# sk9822.net
KiCad netlist of a schematic drawn in Altium Designer
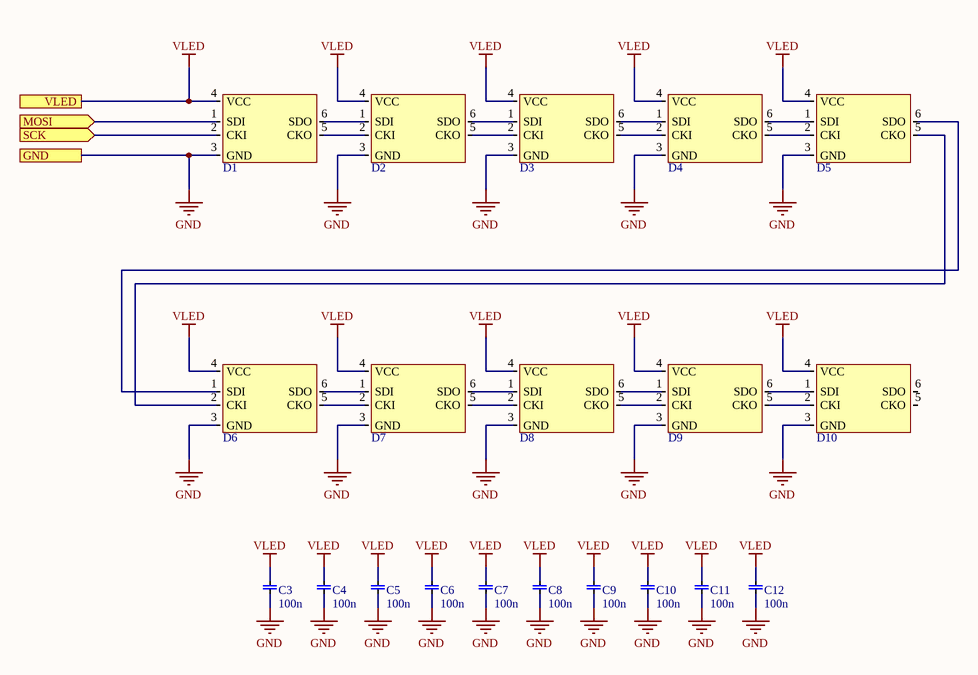
[diagram p0: sk9822.SchDoc]

(export (version "E")
  (design (tool "Eeschema 10.0.6"))
  (components
    (comp (ref "C3")
      (value "100n")
      (footprint "1206, capasitor")
      (fields
        (field (name "JLCPCB PART #") "C24497")
        (field (name "MANUFACTURER PART NUMBER") "CL31B104KBCNNNC")
        (field (name "Comment") "1206, capacitor")
      )
      (libsource (lib "jclib") (part "1206, capacitor"))
    )
    (comp (ref "C4")
      (value "100n")
      (footprint "1206, capasitor")
      (fields
        (field (name "JLCPCB PART #") "C24497")
        (field (name "MANUFACTURER PART NUMBER") "CL31B104KBCNNNC")
        (field (name "Comment") "1206, capacitor")
      )
      (libsource (lib "jclib") (part "1206, capacitor"))
    )
    (comp (ref "C5")
      (value "100n")
      (footprint "1206, capasitor")
      (fields
        (field (name "JLCPCB PART #") "C24497")
        (field (name "MANUFACTURER PART NUMBER") "CL31B104KBCNNNC")
        (field (name "Comment") "1206, capacitor")
      )
      (libsource (lib "jclib") (part "1206, capacitor"))
    )
    (comp (ref "C6")
      (value "100n")
      (footprint "1206, capasitor")
      (fields
        (field (name "JLCPCB PART #") "C24497")
        (field (name "MANUFACTURER PART NUMBER") "CL31B104KBCNNNC")
        (field (name "Comment") "1206, capacitor")
      )
      (libsource (lib "jclib") (part "1206, capacitor"))
    )
    (comp (ref "C7")
      (value "100n")
      (footprint "1206, capasitor")
      (fields
        (field (name "JLCPCB PART #") "C24497")
        (field (name "MANUFACTURER PART NUMBER") "CL31B104KBCNNNC")
        (field (name "Comment") "1206, capacitor")
      )
      (libsource (lib "jclib") (part "1206, capacitor"))
    )
    (comp (ref "C8")
      (value "100n")
      (footprint "1206, capasitor")
      (fields
        (field (name "JLCPCB PART #") "C24497")
        (field (name "MANUFACTURER PART NUMBER") "CL31B104KBCNNNC")
        (field (name "Comment") "1206, capacitor")
      )
      (libsource (lib "jclib") (part "1206, capacitor"))
    )
    (comp (ref "C9")
      (value "100n")
      (footprint "1206, capasitor")
      (fields
        (field (name "JLCPCB PART #") "C24497")
        (field (name "MANUFACTURER PART NUMBER") "CL31B104KBCNNNC")
        (field (name "Comment") "1206, capacitor")
      )
      (libsource (lib "jclib") (part "1206, capacitor"))
    )
    (comp (ref "C10")
      (value "100n")
      (footprint "1206, capasitor")
      (fields
        (field (name "JLCPCB PART #") "C24497")
        (field (name "MANUFACTURER PART NUMBER") "CL31B104KBCNNNC")
        (field (name "Comment") "1206, capacitor")
      )
      (libsource (lib "jclib") (part "1206, capacitor"))
    )
    (comp (ref "C11")
      (value "100n")
      (footprint "1206, capasitor")
      (fields
        (field (name "JLCPCB PART #") "C24497")
        (field (name "MANUFACTURER PART NUMBER") "CL31B104KBCNNNC")
        (field (name "Comment") "1206, capacitor")
      )
      (libsource (lib "jclib") (part "1206, capacitor"))
    )
    (comp (ref "C12")
      (value "100n")
      (footprint "1206, capasitor")
      (fields
        (field (name "JLCPCB PART #") "C24497")
        (field (name "MANUFACTURER PART NUMBER") "CL31B104KBCNNNC")
        (field (name "Comment") "1206, capacitor")
      )
      (libsource (lib "jclib") (part "1206, capacitor"))
    )
    (comp (ref "D1")
      (value "Neo - SK9822")
      (footprint "SK9822")
      (fields (field (name "JLCPCB PART #") "C2829089") (field (name "MANUFACTURER PART NUMBER") "SK9822"))
      (libsource (lib "jclib") (part "Neo - SK9822"))
    )
    (comp (ref "D2")
      (value "Neo - SK9822")
      (footprint "SK9822")
      (fields (field (name "JLCPCB PART #") "C2829089") (field (name "MANUFACTURER PART NUMBER") "SK9822"))
      (libsource (lib "jclib") (part "Neo - SK9822"))
    )
    (comp (ref "D3")
      (value "Neo - SK9822")
      (footprint "SK9822")
      (fields (field (name "JLCPCB PART #") "C2829089") (field (name "MANUFACTURER PART NUMBER") "SK9822"))
      (libsource (lib "jclib") (part "Neo - SK9822"))
    )
    (comp (ref "D4")
      (value "Neo - SK9822")
      (footprint "SK9822")
      (fields (field (name "JLCPCB PART #") "C2829089") (field (name "MANUFACTURER PART NUMBER") "SK9822"))
      (libsource (lib "jclib") (part "Neo - SK9822"))
    )
    (comp (ref "D5")
      (value "Neo - SK9822")
      (footprint "SK9822")
      (fields (field (name "JLCPCB PART #") "C2829089") (field (name "MANUFACTURER PART NUMBER") "SK9822"))
      (libsource (lib "jclib") (part "Neo - SK9822"))
    )
    (comp (ref "D6")
      (value "Neo - SK9822")
      (footprint "SK9822")
      (fields (field (name "JLCPCB PART #") "C2829089") (field (name "MANUFACTURER PART NUMBER") "SK9822"))
      (libsource (lib "jclib") (part "Neo - SK9822"))
    )
    (comp (ref "D7")
      (value "Neo - SK9822")
      (footprint "SK9822")
      (fields (field (name "JLCPCB PART #") "C2829089") (field (name "MANUFACTURER PART NUMBER") "SK9822"))
      (libsource (lib "jclib") (part "Neo - SK9822"))
    )
    (comp (ref "D8")
      (value "Neo - SK9822")
      (footprint "SK9822")
      (fields (field (name "JLCPCB PART #") "C2829089") (field (name "MANUFACTURER PART NUMBER") "SK9822"))
      (libsource (lib "jclib") (part "Neo - SK9822"))
    )
    (comp (ref "D9")
      (value "Neo - SK9822")
      (footprint "SK9822")
      (fields (field (name "JLCPCB PART #") "C2829089") (field (name "MANUFACTURER PART NUMBER") "SK9822"))
      (libsource (lib "jclib") (part "Neo - SK9822"))
    )
    (comp (ref "D10")
      (value "Neo - SK9822")
      (footprint "SK9822")
      (fields (field (name "JLCPCB PART #") "C2829089") (field (name "MANUFACTURER PART NUMBER") "SK9822"))
      (libsource (lib "jclib") (part "Neo - SK9822"))
    )
  )
  (nets
    (net (code "1") (name "/MOSI") (class "Default")
      (node (ref "D1") (pin "1") (pinfunction "SDI_1") (pintype "passive"))
    )
    (net (code "2") (name "/SCK") (class "Default")
      (node (ref "D1") (pin "2") (pinfunction "CKI_2") (pintype "passive"))
    )
    (net (code "3") (name "GND") (class "Default")
      (node (ref "C10") (pin "0") (pinfunction "0_0") (pintype "passive"))
      (node (ref "C11") (pin "0") (pinfunction "0_0") (pintype "passive"))
      (node (ref "C12") (pin "0") (pinfunction "0_0") (pintype "passive"))
      (node (ref "C3") (pin "0") (pinfunction "0_0") (pintype "passive"))
      (node (ref "C4") (pin "0") (pinfunction "0_0") (pintype "passive"))
      (node (ref "C5") (pin "0") (pinfunction "0_0") (pintype "passive"))
      (node (ref "C6") (pin "0") (pinfunction "0_0") (pintype "passive"))
      (node (ref "C7") (pin "0") (pinfunction "0_0") (pintype "passive"))
      (node (ref "C8") (pin "0") (pinfunction "0_0") (pintype "passive"))
      (node (ref "C9") (pin "0") (pinfunction "0_0") (pintype "passive"))
      (node (ref "D1") (pin "3") (pinfunction "GND_3") (pintype "passive"))
      (node (ref "D10") (pin "3") (pinfunction "GND_3") (pintype "passive"))
      (node (ref "D2") (pin "3") (pinfunction "GND_3") (pintype "passive"))
      (node (ref "D3") (pin "3") (pinfunction "GND_3") (pintype "passive"))
      (node (ref "D4") (pin "3") (pinfunction "GND_3") (pintype "passive"))
      (node (ref "D5") (pin "3") (pinfunction "GND_3") (pintype "passive"))
      (node (ref "D6") (pin "3") (pinfunction "GND_3") (pintype "passive"))
      (node (ref "D7") (pin "3") (pinfunction "GND_3") (pintype "passive"))
      (node (ref "D8") (pin "3") (pinfunction "GND_3") (pintype "passive"))
      (node (ref "D9") (pin "3") (pinfunction "GND_3") (pintype "passive"))
    )
    (net (code "4") (name "Net-(D1-CKO)") (class "Default")
      (node (ref "D1") (pin "5") (pinfunction "CKO_5") (pintype "passive"))
      (node (ref "D2") (pin "2") (pinfunction "CKI_2") (pintype "passive"))
    )
    (net (code "5") (name "Net-(D1-SDO)") (class "Default")
      (node (ref "D1") (pin "6") (pinfunction "SDO_6") (pintype "passive"))
      (node (ref "D2") (pin "1") (pinfunction "SDI_1") (pintype "passive"))
    )
    (net (code "6") (name "Net-(D2-CKO)") (class "Default")
      (node (ref "D2") (pin "5") (pinfunction "CKO_5") (pintype "passive"))
      (node (ref "D3") (pin "2") (pinfunction "CKI_2") (pintype "passive"))
    )
    (net (code "7") (name "Net-(D2-SDO)") (class "Default")
      (node (ref "D2") (pin "6") (pinfunction "SDO_6") (pintype "passive"))
      (node (ref "D3") (pin "1") (pinfunction "SDI_1") (pintype "passive"))
    )
    (net (code "8") (name "Net-(D3-CKO)") (class "Default")
      (node (ref "D3") (pin "5") (pinfunction "CKO_5") (pintype "passive"))
      (node (ref "D4") (pin "2") (pinfunction "CKI_2") (pintype "passive"))
    )
    (net (code "9") (name "Net-(D3-SDO)") (class "Default")
      (node (ref "D3") (pin "6") (pinfunction "SDO_6") (pintype "passive"))
      (node (ref "D4") (pin "1") (pinfunction "SDI_1") (pintype "passive"))
    )
    (net (code "10") (name "Net-(D4-CKO)") (class "Default")
      (node (ref "D4") (pin "5") (pinfunction "CKO_5") (pintype "passive"))
      (node (ref "D5") (pin "2") (pinfunction "CKI_2") (pintype "passive"))
    )
    (net (code "11") (name "Net-(D4-SDO)") (class "Default")
      (node (ref "D4") (pin "6") (pinfunction "SDO_6") (pintype "passive"))
      (node (ref "D5") (pin "1") (pinfunction "SDI_1") (pintype "passive"))
    )
    (net (code "12") (name "Net-(D5-CKO)") (class "Default")
      (node (ref "D5") (pin "5") (pinfunction "CKO_5") (pintype "passive"))
      (node (ref "D6") (pin "2") (pinfunction "CKI_2") (pintype "passive"))
    )
    (net (code "13") (name "Net-(D5-SDO)") (class "Default")
      (node (ref "D5") (pin "6") (pinfunction "SDO_6") (pintype "passive"))
      (node (ref "D6") (pin "1") (pinfunction "SDI_1") (pintype "passive"))
    )
    (net (code "14") (name "Net-(D6-CKO)") (class "Default")
      (node (ref "D6") (pin "5") (pinfunction "CKO_5") (pintype "passive"))
      (node (ref "D7") (pin "2") (pinfunction "CKI_2") (pintype "passive"))
    )
    (net (code "15") (name "Net-(D6-SDO)") (class "Default")
      (node (ref "D6") (pin "6") (pinfunction "SDO_6") (pintype "passive"))
      (node (ref "D7") (pin "1") (pinfunction "SDI_1") (pintype "passive"))
    )
    (net (code "16") (name "Net-(D7-CKO)") (class "Default")
      (node (ref "D7") (pin "5") (pinfunction "CKO_5") (pintype "passive"))
      (node (ref "D8") (pin "2") (pinfunction "CKI_2") (pintype "passive"))
    )
    (net (code "17") (name "Net-(D7-SDO)") (class "Default")
      (node (ref "D7") (pin "6") (pinfunction "SDO_6") (pintype "passive"))
      (node (ref "D8") (pin "1") (pinfunction "SDI_1") (pintype "passive"))
    )
    (net (code "18") (name "Net-(D8-CKO)") (class "Default")
      (node (ref "D8") (pin "5") (pinfunction "CKO_5") (pintype "passive"))
      (node (ref "D9") (pin "2") (pinfunction "CKI_2") (pintype "passive"))
    )
    (net (code "19") (name "Net-(D8-SDO)") (class "Default")
      (node (ref "D8") (pin "6") (pinfunction "SDO_6") (pintype "passive"))
      (node (ref "D9") (pin "1") (pinfunction "SDI_1") (pintype "passive"))
    )
    (net (code "20") (name "Net-(D10-CKI)") (class "Default")
      (node (ref "D10") (pin "2") (pinfunction "CKI_2") (pintype "passive"))
      (node (ref "D9") (pin "5") (pinfunction "CKO_5") (pintype "passive"))
    )
    (net (code "21") (name "Net-(D10-SDI)") (class "Default")
      (node (ref "D10") (pin "1") (pinfunction "SDI_1") (pintype "passive"))
      (node (ref "D9") (pin "6") (pinfunction "SDO_6") (pintype "passive"))
    )
    (net (code "22") (name "VLED") (class "Default")
      (node (ref "C10") (pin "1") (pinfunction "1_1") (pintype "passive"))
      (node (ref "C11") (pin "1") (pinfunction "1_1") (pintype "passive"))
      (node (ref "C12") (pin "1") (pinfunction "1_1") (pintype "passive"))
      (node (ref "C3") (pin "1") (pinfunction "1_1") (pintype "passive"))
      (node (ref "C4") (pin "1") (pinfunction "1_1") (pintype "passive"))
      (node (ref "C5") (pin "1") (pinfunction "1_1") (pintype "passive"))
      (node (ref "C6") (pin "1") (pinfunction "1_1") (pintype "passive"))
      (node (ref "C7") (pin "1") (pinfunction "1_1") (pintype "passive"))
      (node (ref "C8") (pin "1") (pinfunction "1_1") (pintype "passive"))
      (node (ref "C9") (pin "1") (pinfunction "1_1") (pintype "passive"))
      (node (ref "D1") (pin "4") (pinfunction "VCC_4") (pintype "passive"))
      (node (ref "D10") (pin "4") (pinfunction "VCC_4") (pintype "passive"))
      (node (ref "D2") (pin "4") (pinfunction "VCC_4") (pintype "passive"))
      (node (ref "D3") (pin "4") (pinfunction "VCC_4") (pintype "passive"))
      (node (ref "D4") (pin "4") (pinfunction "VCC_4") (pintype "passive"))
      (node (ref "D5") (pin "4") (pinfunction "VCC_4") (pintype "passive"))
      (node (ref "D6") (pin "4") (pinfunction "VCC_4") (pintype "passive"))
      (node (ref "D7") (pin "4") (pinfunction "VCC_4") (pintype "passive"))
      (node (ref "D8") (pin "4") (pinfunction "VCC_4") (pintype "passive"))
      (node (ref "D9") (pin "4") (pinfunction "VCC_4") (pintype "passive"))
    )
    (net (code "23") (name "unconnected-(D10-CKO-Pad5)") (class "Default")
      (node (ref "D10") (pin "5") (pinfunction "CKO_5") (pintype "passive"))
    )
    (net (code "24") (name "unconnected-(D10-SDO-Pad6)") (class "Default")
      (node (ref "D10") (pin "6") (pinfunction "SDO_6") (pintype "passive"))
    )
  )
)
